# Track_Controller.net
KiCad netlist of a schematic drawn in EAGLE
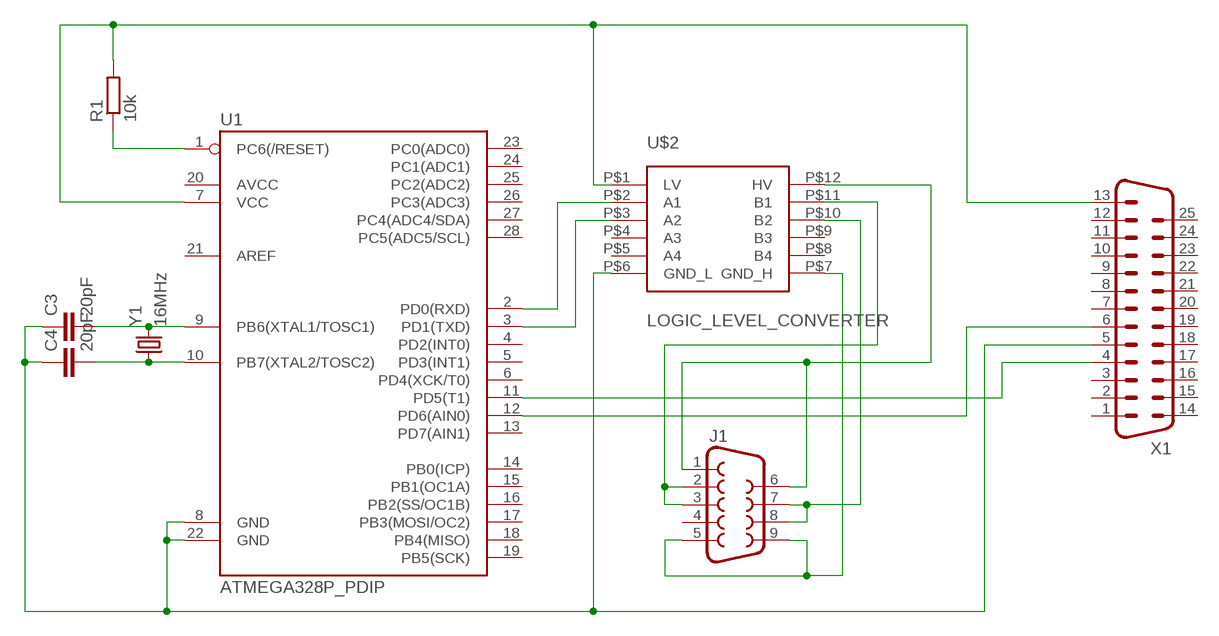
[diagram p0: schematic, sheet 1]
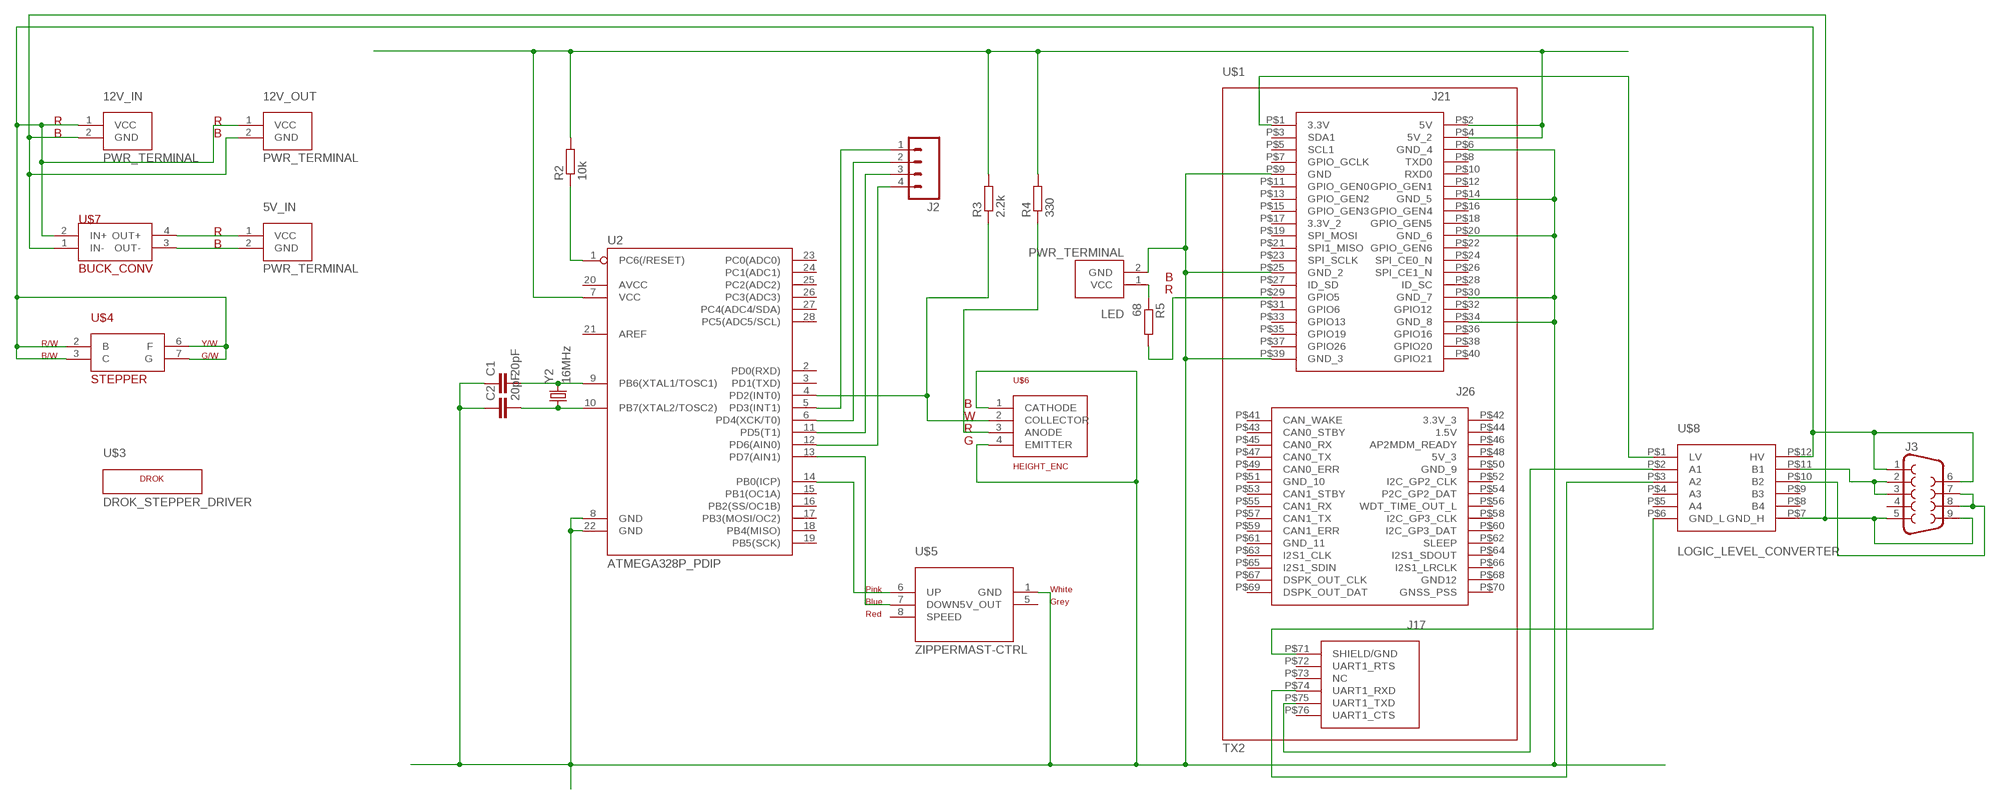
[diagram p1: schematic, sheet 2]

(export (version "E")
  (design (tool "Eeschema 10.0.6"))
  (components
    (comp (ref "5V_IN")
      (value "PWR_TERMINAL")
      (footprint "eagle-import:PWR_TERMINAL")
      (libsource (lib "eagle-import") (part "PWR_TERMINAL"))
    )
    (comp (ref "12V_IN")
      (value "PWR_TERMINAL")
      (footprint "eagle-import:PWR_TERMINAL")
      (libsource (lib "eagle-import") (part "PWR_TERMINAL"))
    )
    (comp (ref "12V_OUT")
      (value "PWR_TERMINAL")
      (footprint "eagle-import:PWR_TERMINAL")
      (libsource (lib "eagle-import") (part "PWR_TERMINAL"))
    )
    (comp (ref "C1")
      (value "20pF")
      (footprint "eagle-import:CAP-PTH-5MM")
      (libsource (lib "eagle-import") (part "CAPPTH1"))
    )
    (comp (ref "C2")
      (value "20pF")
      (footprint "eagle-import:CAP-PTH-5MM")
      (libsource (lib "eagle-import") (part "CAPPTH1"))
    )
    (comp (ref "J2")
      (value "M04PTH")
      (footprint "eagle-import:1X04")
      (libsource (lib "eagle-import") (part "M04PTH"))
    )
    (comp (ref "J3")
      (value "DB9MALE")
      (footprint "eagle-import:DB9_MALE")
      (libsource (lib "eagle-import") (part "DB9MALE"))
    )
    (comp (ref "LED")
      (value "PWR_TERMINAL")
      (footprint "eagle-import:PWR_TERMINAL")
      (libsource (lib "eagle-import") (part "PWR_TERMINAL"))
    )
    (comp (ref "R2")
      (value "10k")
      (footprint "eagle-import:0204_7")
      (libsource (lib "eagle-import") (part "R-EU_0204/7"))
    )
    (comp (ref "R3")
      (value "2.2k")
      (footprint "eagle-import:0204_7")
      (libsource (lib "eagle-import") (part "R-EU_0204/7"))
    )
    (comp (ref "R4")
      (value "330")
      (footprint "eagle-import:0204_7")
      (libsource (lib "eagle-import") (part "R-EU_0204/7"))
    )
    (comp (ref "R5")
      (value "68")
      (footprint "eagle-import:0204_7")
      (libsource (lib "eagle-import") (part "R-EU_0204/7"))
    )
    (comp (ref "U$1")
      (value "TX2")
      (footprint "eagle-import:TX2")
      (libsource (lib "eagle-import") (part "TX2"))
    )
    (comp (ref "U$3")
      (value "DROK_STEPPER_DRIVER")
      (footprint "eagle-import:DROK_STEPPER_DRIVER")
      (libsource (lib "eagle-import") (part "DROK_STEPPER_DRIVER"))
    )
    (comp (ref "U$4")
      (value "STEPPER")
      (footprint "eagle-import:STEPPER")
      (libsource (lib "eagle-import") (part "STEPPER"))
    )
    (comp (ref "U$5")
      (value "ZIPPERMAST-CTRL")
      (footprint "eagle-import:ZIPPERMAST-CTRL")
      (libsource (lib "eagle-import") (part "ZIPPERMAST-CTRL"))
    )
    (comp (ref "U$6")
      (value "HEIGHT_ENC")
      (footprint "eagle-import:HEIGHT_ENC")
      (libsource (lib "eagle-import") (part "HEIGHT_ENC"))
    )
    (comp (ref "U$7")
      (value "BUCK_CONV")
      (footprint "eagle-import:BUCK_CONV")
      (libsource (lib "eagle-import") (part "BUCK_CONV"))
    )
    (comp (ref "U$8")
      (value "LOGIC_LEVEL_CONVERTER")
      (footprint "eagle-import:LOGIC_LEVEL_CONVERTER")
      (libsource (lib "eagle-import") (part "LOGIC_LEVEL_CONVERTER"))
    )
    (comp (ref "U2")
      (value "ATMEGA328P_PDIP")
      (footprint "eagle-import:DIL28-3")
      (libsource (lib "eagle-import") (part "ATMEGA328P_PDIP"))
    )
    (comp (ref "Y2")
      (value "16MHz")
      (footprint "eagle-import:HC49US")
      (libsource (lib "eagle-import") (part "CRYSTALHC49US"))
    )
    (comp (ref "C3")
      (value "20pF")
      (footprint "eagle-import:CAP-PTH-5MM")
      (libsource (lib "eagle-import") (part "CAPPTH1"))
    )
    (comp (ref "C4")
      (value "20pF")
      (footprint "eagle-import:CAP-PTH-5MM")
      (libsource (lib "eagle-import") (part "CAPPTH1"))
    )
    (comp (ref "J1")
      (value "DB9FEMALE")
      (footprint "eagle-import:DB9")
      (libsource (lib "eagle-import") (part "DB9FEMALE"))
    )
    (comp (ref "R1")
      (value "10k")
      (footprint "eagle-import:0204_7")
      (libsource (lib "eagle-import") (part "R-EU_0204/7"))
    )
    (comp (ref "U$2")
      (value "LOGIC_LEVEL_CONVERTER")
      (footprint "eagle-import:LOGIC_LEVEL_CONVERTER")
      (libsource (lib "eagle-import") (part "LOGIC_LEVEL_CONVERTER"))
    )
    (comp (ref "U1")
      (value "ATMEGA328P_PDIP")
      (footprint "eagle-import:DIL28-3")
      (libsource (lib "eagle-import") (part "ATMEGA328P_PDIP"))
    )
    (comp (ref "X1")
      (value "DB25H")
      (footprint "eagle-import:M25H")
      (libsource (lib "eagle-import") (part "DB25H"))
    )
    (comp (ref "Y1")
      (value "16MHz")
      (footprint "eagle-import:HC49US")
      (libsource (lib "eagle-import") (part "CRYSTALHC49US"))
    )
  )
  (nets
    (net (code "1") (name "Net-(5V_IN-GND)") (class "Default")
      (node (ref "5V_IN") (pin "2") (pinfunction "GND_2") (pintype "bidirectional"))
      (node (ref "U$7") (pin "3") (pinfunction "OUT-_3") (pintype "bidirectional"))
    )
    (net (code "2") (name "Net-(5V_IN-VCC)") (class "Default")
      (node (ref "5V_IN") (pin "1") (pinfunction "VCC_1") (pintype "bidirectional"))
      (node (ref "U$7") (pin "4") (pinfunction "OUT+_4") (pintype "bidirectional"))
    )
    (net (code "3") (name "Net-(12V_IN-GND)") (class "Default")
      (node (ref "12V_IN") (pin "2") (pinfunction "GND_2") (pintype "bidirectional"))
      (node (ref "12V_OUT") (pin "2") (pinfunction "GND_2") (pintype "bidirectional"))
      (node (ref "J3") (pin "5") (pinfunction "5_5") (pintype "passive"))
      (node (ref "J3") (pin "9") (pinfunction "9_9") (pintype "passive"))
      (node (ref "U$7") (pin "1") (pinfunction "IN-_1") (pintype "bidirectional"))
      (node (ref "U$8") (pin "P$7") (pinfunction "GND_H_P$7") (pintype "bidirectional"))
    )
    (net (code "4") (name "Net-(12V_IN-VCC)") (class "Default")
      (node (ref "12V_IN") (pin "1") (pinfunction "VCC_1") (pintype "bidirectional"))
      (node (ref "12V_OUT") (pin "1") (pinfunction "VCC_1") (pintype "bidirectional"))
      (node (ref "J3") (pin "1") (pinfunction "1_1") (pintype "passive"))
      (node (ref "J3") (pin "6") (pinfunction "6_6") (pintype "passive"))
      (node (ref "U$4") (pin "2") (pinfunction "B_2") (pintype "bidirectional"))
      (node (ref "U$4") (pin "3") (pinfunction "C_3") (pintype "bidirectional"))
      (node (ref "U$4") (pin "6") (pinfunction "F_6") (pintype "bidirectional"))
      (node (ref "U$4") (pin "7") (pinfunction "G_7") (pintype "bidirectional"))
      (node (ref "U$7") (pin "2") (pinfunction "IN+_2") (pintype "bidirectional"))
      (node (ref "U$8") (pin "P$12") (pinfunction "HV_P$12") (pintype "bidirectional"))
    )
    (net (code "5") (name "Net-(LED-GND)") (class "Default")
      (node (ref "C1") (pin "1") (pinfunction "1_1") (pintype "passive"))
      (node (ref "C2") (pin "1") (pinfunction "1_1") (pintype "passive"))
      (node (ref "LED") (pin "2") (pinfunction "GND_2") (pintype "bidirectional"))
      (node (ref "U$1") (pin "P$14") (pinfunction "GND_5_P$14") (pintype "bidirectional"))
      (node (ref "U$1") (pin "P$20") (pinfunction "GND_6_P$20") (pintype "bidirectional"))
      (node (ref "U$1") (pin "P$25") (pinfunction "GND_2_P$25") (pintype "bidirectional"))
      (node (ref "U$1") (pin "P$30") (pinfunction "GND_7_P$30") (pintype "bidirectional"))
      (node (ref "U$1") (pin "P$34") (pinfunction "GND_8_P$34") (pintype "bidirectional"))
      (node (ref "U$1") (pin "P$39") (pinfunction "GND_3_P$39") (pintype "bidirectional"))
      (node (ref "U$1") (pin "P$6") (pinfunction "GND_4_P$6") (pintype "bidirectional"))
      (node (ref "U$1") (pin "P$9") (pinfunction "GND_P$9") (pintype "bidirectional"))
      (node (ref "U$5") (pin "1") (pinfunction "GND_1") (pintype "bidirectional"))
      (node (ref "U$6") (pin "1") (pinfunction "CATHODE_1") (pintype "bidirectional"))
      (node (ref "U$6") (pin "4") (pinfunction "EMITTER_4") (pintype "bidirectional"))
      (node (ref "U2") (pin "22") (pinfunction "GND_22") (pintype "bidirectional"))
      (node (ref "U2") (pin "8") (pinfunction "GND_8") (pintype "bidirectional"))
    )
    (net (code "6") (name "Net-(LED-VCC)") (class "Default")
      (node (ref "LED") (pin "1") (pinfunction "VCC_1") (pintype "bidirectional"))
      (node (ref "R5") (pin "1") (pinfunction "1_1") (pintype "passive"))
    )
    (net (code "7") (name "Net-(U$1-3.3V)") (class "Default")
      (node (ref "U$1") (pin "P$1") (pinfunction "3.3V_P$1") (pintype "bidirectional"))
      (node (ref "U$8") (pin "P$1") (pinfunction "LV_P$1") (pintype "bidirectional"))
    )
    (net (code "8") (name "Net-(U$1-5V)") (class "Default")
      (node (ref "R2") (pin "2") (pinfunction "2_2") (pintype "passive"))
      (node (ref "R3") (pin "2") (pinfunction "2_2") (pintype "passive"))
      (node (ref "R4") (pin "2") (pinfunction "2_2") (pintype "passive"))
      (node (ref "U$1") (pin "P$2") (pinfunction "5V_P$2") (pintype "bidirectional"))
      (node (ref "U$1") (pin "P$4") (pinfunction "5V_2_P$4") (pintype "bidirectional"))
      (node (ref "U2") (pin "7") (pinfunction "VCC_7") (pintype "bidirectional"))
    )
    (net (code "9") (name "Net-(U$1-GPIO5)") (class "Default")
      (node (ref "R5") (pin "2") (pinfunction "2_2") (pintype "passive"))
      (node (ref "U$1") (pin "P$29") (pinfunction "GPIO5_P$29") (pintype "bidirectional"))
    )
    (net (code "10") (name "Net-(U$1-SHIELD{slash}GND)") (class "Default")
      (node (ref "U$1") (pin "P$71") (pinfunction "SHIELD/GND_P$71") (pintype "bidirectional"))
      (node (ref "U$8") (pin "P$6") (pinfunction "GND_L_P$6") (pintype "bidirectional"))
    )
    (net (code "11") (name "Net-(U$1-UART1_RXD)") (class "Default")
      (node (ref "U$1") (pin "P$74") (pinfunction "UART1_RXD_P$74") (pintype "bidirectional"))
      (node (ref "U$8") (pin "P$3") (pinfunction "A2_P$3") (pintype "bidirectional"))
    )
    (net (code "12") (name "Net-(U$1-UART1_TXD)") (class "Default")
      (node (ref "U$1") (pin "P$75") (pinfunction "UART1_TXD_P$75") (pintype "bidirectional"))
      (node (ref "U$8") (pin "P$2") (pinfunction "A1_P$2") (pintype "bidirectional"))
    )
    (net (code "13") (name "Net-(U$2-A1)") (class "Default")
      (node (ref "U$2") (pin "P$2") (pinfunction "A1_P$2") (pintype "bidirectional"))
      (node (ref "U1") (pin "2") (pinfunction "PD0(RXD)_2") (pintype "bidirectional"))
    )
    (net (code "14") (name "Net-(U$2-A2)") (class "Default")
      (node (ref "U$2") (pin "P$3") (pinfunction "A2_P$3") (pintype "bidirectional"))
      (node (ref "U1") (pin "3") (pinfunction "PD1(TXD)_3") (pintype "bidirectional"))
    )
    (net (code "15") (name "Net-(U$2-B1)") (class "Default")
      (node (ref "J1") (pin "2") (pinfunction "2_2") (pintype "passive"))
      (node (ref "J1") (pin "3") (pinfunction "3_3") (pintype "passive"))
      (node (ref "U$2") (pin "P$11") (pinfunction "B1_P$11") (pintype "bidirectional"))
    )
    (net (code "16") (name "Net-(U$2-B2)") (class "Default")
      (node (ref "J1") (pin "7") (pinfunction "7_7") (pintype "passive"))
      (node (ref "J1") (pin "8") (pinfunction "8_8") (pintype "passive"))
      (node (ref "U$2") (pin "P$10") (pinfunction "B2_P$10") (pintype "bidirectional"))
    )
    (net (code "17") (name "Net-(U$2-GND_H)") (class "Default")
      (node (ref "J1") (pin "5") (pinfunction "5_5") (pintype "passive"))
      (node (ref "J1") (pin "9") (pinfunction "9_9") (pintype "passive"))
      (node (ref "U$2") (pin "P$7") (pinfunction "GND_H_P$7") (pintype "bidirectional"))
    )
    (net (code "18") (name "Net-(U$2-GND_L)") (class "Default")
      (node (ref "C3") (pin "1") (pinfunction "1_1") (pintype "passive"))
      (node (ref "C4") (pin "1") (pinfunction "1_1") (pintype "passive"))
      (node (ref "U$2") (pin "P$6") (pinfunction "GND_L_P$6") (pintype "bidirectional"))
      (node (ref "U1") (pin "22") (pinfunction "GND_22") (pintype "bidirectional"))
      (node (ref "U1") (pin "8") (pinfunction "GND_8") (pintype "bidirectional"))
      (node (ref "X1") (pin "5") (pinfunction "5_5") (pintype "passive"))
    )
    (net (code "19") (name "Net-(U$2-HV)") (class "Default")
      (node (ref "J1") (pin "1") (pinfunction "1_1") (pintype "passive"))
      (node (ref "J1") (pin "6") (pinfunction "6_6") (pintype "passive"))
      (node (ref "U$2") (pin "P$12") (pinfunction "HV_P$12") (pintype "bidirectional"))
    )
    (net (code "20") (name "Net-(U$2-LV)") (class "Default")
      (node (ref "R1") (pin "2") (pinfunction "2_2") (pintype "passive"))
      (node (ref "U$2") (pin "P$1") (pinfunction "LV_P$1") (pintype "bidirectional"))
      (node (ref "U1") (pin "7") (pinfunction "VCC_7") (pintype "bidirectional"))
      (node (ref "X1") (pin "13") (pinfunction "13_13") (pintype "passive"))
    )
    (net (code "21") (name "Net-(U$5-DOWN)") (class "Default")
      (node (ref "U$5") (pin "7") (pinfunction "DOWN_7") (pintype "bidirectional"))
      (node (ref "U2") (pin "13") (pinfunction "PD7(AIN1)_13") (pintype "bidirectional"))
    )
    (net (code "22") (name "Net-(U$5-UP)") (class "Default")
      (node (ref "U$5") (pin "6") (pinfunction "UP_6") (pintype "bidirectional"))
      (node (ref "U2") (pin "14") (pinfunction "PB0(ICP)_14") (pintype "bidirectional"))
    )
    (net (code "23") (name "Net-(U$6-ANODE)") (class "Default")
      (node (ref "R4") (pin "1") (pinfunction "1_1") (pintype "passive"))
      (node (ref "U$6") (pin "3") (pinfunction "ANODE_3") (pintype "bidirectional"))
    )
    (net (code "24") (name "Net-(U$6-COLLECTOR)") (class "Default")
      (node (ref "R3") (pin "1") (pinfunction "1_1") (pintype "passive"))
      (node (ref "U$6") (pin "2") (pinfunction "COLLECTOR_2") (pintype "bidirectional"))
      (node (ref "U2") (pin "4") (pinfunction "PD2(INT0)_4") (pintype "bidirectional"))
    )
    (net (code "25") (name "Net-(U$8-B1)") (class "Default")
      (node (ref "J3") (pin "2") (pinfunction "2_2") (pintype "passive"))
      (node (ref "J3") (pin "3") (pinfunction "3_3") (pintype "passive"))
      (node (ref "U$8") (pin "P$11") (pinfunction "B1_P$11") (pintype "bidirectional"))
    )
    (net (code "26") (name "Net-(U$8-B2)") (class "Default")
      (node (ref "J3") (pin "7") (pinfunction "7_7") (pintype "passive"))
      (node (ref "J3") (pin "8") (pinfunction "8_8") (pintype "passive"))
      (node (ref "U$8") (pin "P$10") (pinfunction "B2_P$10") (pintype "bidirectional"))
    )
    (net (code "27") (name "Net-(U1-PB6(XTAL1{slash}TOSC1))") (class "Default")
      (node (ref "C3") (pin "2") (pinfunction "2_2") (pintype "passive"))
      (node (ref "U1") (pin "9") (pinfunction "PB6(XTAL1/TOSC1)_9") (pintype "bidirectional"))
      (node (ref "Y1") (pin "2") (pinfunction "2_2") (pintype "passive"))
    )
    (net (code "28") (name "Net-(U1-PB7(XTAL2{slash}TOSC2))") (class "Default")
      (node (ref "C4") (pin "2") (pinfunction "2_2") (pintype "passive"))
      (node (ref "U1") (pin "10") (pinfunction "PB7(XTAL2/TOSC2)_10") (pintype "bidirectional"))
      (node (ref "Y1") (pin "1") (pinfunction "1_1") (pintype "passive"))
    )
    (net (code "29") (name "Net-(U1-PC6({slash}RESET))") (class "Default")
      (node (ref "R1") (pin "1") (pinfunction "1_1") (pintype "passive"))
      (node (ref "U1") (pin "1") (pinfunction "PC6(/RESET)_1") (pintype "bidirectional"))
    )
    (net (code "30") (name "Net-(U1-PD5(T1))") (class "Default")
      (node (ref "U1") (pin "11") (pinfunction "PD5(T1)_11") (pintype "bidirectional"))
      (node (ref "X1") (pin "4") (pinfunction "4_4") (pintype "passive"))
    )
    (net (code "31") (name "Net-(U1-PD6(AIN0))") (class "Default")
      (node (ref "U1") (pin "12") (pinfunction "PD6(AIN0)_12") (pintype "bidirectional"))
      (node (ref "X1") (pin "6") (pinfunction "6_6") (pintype "passive"))
    )
    (net (code "32") (name "Net-(U2-PB6(XTAL1{slash}TOSC1))") (class "Default")
      (node (ref "C1") (pin "2") (pinfunction "2_2") (pintype "passive"))
      (node (ref "U2") (pin "9") (pinfunction "PB6(XTAL1/TOSC1)_9") (pintype "bidirectional"))
      (node (ref "Y2") (pin "2") (pinfunction "2_2") (pintype "passive"))
    )
    (net (code "33") (name "Net-(U2-PB7(XTAL2{slash}TOSC2))") (class "Default")
      (node (ref "C2") (pin "2") (pinfunction "2_2") (pintype "passive"))
      (node (ref "U2") (pin "10") (pinfunction "PB7(XTAL2/TOSC2)_10") (pintype "bidirectional"))
      (node (ref "Y2") (pin "1") (pinfunction "1_1") (pintype "passive"))
    )
    (net (code "34") (name "Net-(U2-PC6({slash}RESET))") (class "Default")
      (node (ref "R2") (pin "1") (pinfunction "1_1") (pintype "passive"))
      (node (ref "U2") (pin "1") (pinfunction "PC6(/RESET)_1") (pintype "bidirectional"))
    )
    (net (code "35") (name "Net-(U2-PD3(INT1))") (class "Default")
      (node (ref "J2") (pin "1") (pinfunction "1_1") (pintype "passive"))
      (node (ref "U2") (pin "5") (pinfunction "PD3(INT1)_5") (pintype "bidirectional"))
    )
    (net (code "36") (name "Net-(U2-PD4(XCK{slash}T0))") (class "Default")
      (node (ref "J2") (pin "2") (pinfunction "2_2") (pintype "passive"))
      (node (ref "U2") (pin "6") (pinfunction "PD4(XCK/T0)_6") (pintype "bidirectional"))
    )
    (net (code "37") (name "Net-(U2-PD5(T1))") (class "Default")
      (node (ref "J2") (pin "3") (pinfunction "3_3") (pintype "passive"))
      (node (ref "U2") (pin "11") (pinfunction "PD5(T1)_11") (pintype "bidirectional"))
    )
    (net (code "38") (name "Net-(U2-PD6(AIN0))") (class "Default")
      (node (ref "J2") (pin "4") (pinfunction "4_4") (pintype "passive"))
      (node (ref "U2") (pin "12") (pinfunction "PD6(AIN0)_12") (pintype "bidirectional"))
    )
    (net (code "39") (name "unconnected-(J1-Pad4)") (class "Default")
      (node (ref "J1") (pin "4") (pinfunction "4_4") (pintype "passive"))
    )
    (net (code "40") (name "unconnected-(J3-Pad4)") (class "Default")
      (node (ref "J3") (pin "4") (pinfunction "4_4") (pintype "passive"))
    )
    (net (code "41") (name "unconnected-(U$1-1.5V-PadP$44)") (class "Default")
      (node (ref "U$1") (pin "P$44") (pinfunction "1.5V_P$44") (pintype "bidirectional"))
    )
    (net (code "42") (name "unconnected-(U$1-3.3V_2-PadP$17)") (class "Default")
      (node (ref "U$1") (pin "P$17") (pinfunction "3.3V_2_P$17") (pintype "bidirectional"))
    )
    (net (code "43") (name "unconnected-(U$1-3.3V_3-PadP$42)") (class "Default")
      (node (ref "U$1") (pin "P$42") (pinfunction "3.3V_3_P$42") (pintype "bidirectional"))
    )
    (net (code "44") (name "unconnected-(U$1-5V_3-PadP$48)") (class "Default")
      (node (ref "U$1") (pin "P$48") (pinfunction "5V_3_P$48") (pintype "bidirectional"))
    )
    (net (code "45") (name "unconnected-(U$1-AP2MDM_READY-PadP$46)") (class "Default")
      (node (ref "U$1") (pin "P$46") (pinfunction "AP2MDM_READY_P$46") (pintype "bidirectional"))
    )
    (net (code "46") (name "unconnected-(U$1-CAN0_ERR-PadP$49)") (class "Default")
      (node (ref "U$1") (pin "P$49") (pinfunction "CAN0_ERR_P$49") (pintype "bidirectional"))
    )
    (net (code "47") (name "unconnected-(U$1-CAN0_RX-PadP$45)") (class "Default")
      (node (ref "U$1") (pin "P$45") (pinfunction "CAN0_RX_P$45") (pintype "bidirectional"))
    )
    (net (code "48") (name "unconnected-(U$1-CAN0_STBY-PadP$43)") (class "Default")
      (node (ref "U$1") (pin "P$43") (pinfunction "CAN0_STBY_P$43") (pintype "bidirectional"))
    )
    (net (code "49") (name "unconnected-(U$1-CAN0_TX-PadP$47)") (class "Default")
      (node (ref "U$1") (pin "P$47") (pinfunction "CAN0_TX_P$47") (pintype "bidirectional"))
    )
    (net (code "50") (name "unconnected-(U$1-CAN1_ERR-PadP$59)") (class "Default")
      (node (ref "U$1") (pin "P$59") (pinfunction "CAN1_ERR_P$59") (pintype "bidirectional"))
    )
    (net (code "51") (name "unconnected-(U$1-CAN1_RX-PadP$55)") (class "Default")
      (node (ref "U$1") (pin "P$55") (pinfunction "CAN1_RX_P$55") (pintype "bidirectional"))
    )
    (net (code "52") (name "unconnected-(U$1-CAN1_STBY-PadP$53)") (class "Default")
      (node (ref "U$1") (pin "P$53") (pinfunction "CAN1_STBY_P$53") (pintype "bidirectional"))
    )
    (net (code "53") (name "unconnected-(U$1-CAN1_TX-PadP$57)") (class "Default")
      (node (ref "U$1") (pin "P$57") (pinfunction "CAN1_TX_P$57") (pintype "bidirectional"))
    )
    (net (code "54") (name "unconnected-(U$1-CAN_WAKE-PadP$41)") (class "Default")
      (node (ref "U$1") (pin "P$41") (pinfunction "CAN_WAKE_P$41") (pintype "bidirectional"))
    )
    (net (code "55") (name "unconnected-(U$1-DSPK_OUT_CLK-PadP$67)") (class "Default")
      (node (ref "U$1") (pin "P$67") (pinfunction "DSPK_OUT_CLK_P$67") (pintype "bidirectional"))
    )
    (net (code "56") (name "unconnected-(U$1-DSPK_OUT_DAT-PadP$69)") (class "Default")
      (node (ref "U$1") (pin "P$69") (pinfunction "DSPK_OUT_DAT_P$69") (pintype "bidirectional"))
    )
    (net (code "57") (name "unconnected-(U$1-GND12-PadP$68)") (class "Default")
      (node (ref "U$1") (pin "P$68") (pinfunction "GND12_P$68") (pintype "bidirectional"))
    )
    (net (code "58") (name "unconnected-(U$1-GND_9-PadP$50)") (class "Default")
      (node (ref "U$1") (pin "P$50") (pinfunction "GND_9_P$50") (pintype "bidirectional"))
    )
    (net (code "59") (name "unconnected-(U$1-GND_10-PadP$51)") (class "Default")
      (node (ref "U$1") (pin "P$51") (pinfunction "GND_10_P$51") (pintype "bidirectional"))
    )
    (net (code "60") (name "unconnected-(U$1-GND_11-PadP$61)") (class "Default")
      (node (ref "U$1") (pin "P$61") (pinfunction "GND_11_P$61") (pintype "bidirectional"))
    )
    (net (code "61") (name "unconnected-(U$1-GNSS_PSS-PadP$70)") (class "Default")
      (node (ref "U$1") (pin "P$70") (pinfunction "GNSS_PSS_P$70") (pintype "bidirectional"))
    )
    (net (code "62") (name "unconnected-(U$1-GPIO6-PadP$31)") (class "Default")
      (node (ref "U$1") (pin "P$31") (pinfunction "GPIO6_P$31") (pintype "bidirectional"))
    )
    (net (code "63") (name "unconnected-(U$1-GPIO12-PadP$32)") (class "Default")
      (node (ref "U$1") (pin "P$32") (pinfunction "GPIO12_P$32") (pintype "bidirectional"))
    )
    (net (code "64") (name "unconnected-(U$1-GPIO13-PadP$33)") (class "Default")
      (node (ref "U$1") (pin "P$33") (pinfunction "GPIO13_P$33") (pintype "bidirectional"))
    )
    (net (code "65") (name "unconnected-(U$1-GPIO16-PadP$36)") (class "Default")
      (node (ref "U$1") (pin "P$36") (pinfunction "GPIO16_P$36") (pintype "bidirectional"))
    )
    (net (code "66") (name "unconnected-(U$1-GPIO19-PadP$35)") (class "Default")
      (node (ref "U$1") (pin "P$35") (pinfunction "GPIO19_P$35") (pintype "bidirectional"))
    )
    (net (code "67") (name "unconnected-(U$1-GPIO20-PadP$38)") (class "Default")
      (node (ref "U$1") (pin "P$38") (pinfunction "GPIO20_P$38") (pintype "bidirectional"))
    )
    (net (code "68") (name "unconnected-(U$1-GPIO21-PadP$40)") (class "Default")
      (node (ref "U$1") (pin "P$40") (pinfunction "GPIO21_P$40") (pintype "bidirectional"))
    )
    (net (code "69") (name "unconnected-(U$1-GPIO26-PadP$37)") (class "Default")
      (node (ref "U$1") (pin "P$37") (pinfunction "GPIO26_P$37") (pintype "bidirectional"))
    )
    (net (code "70") (name "unconnected-(U$1-GPIO_GCLK-PadP$7)") (class "Default")
      (node (ref "U$1") (pin "P$7") (pinfunction "GPIO_GCLK_P$7") (pintype "bidirectional"))
    )
    (net (code "71") (name "unconnected-(U$1-GPIO_GEN0-PadP$11)") (class "Default")
      (node (ref "U$1") (pin "P$11") (pinfunction "GPIO_GEN0_P$11") (pintype "bidirectional"))
    )
    (net (code "72") (name "unconnected-(U$1-GPIO_GEN1-PadP$12)") (class "Default")
      (node (ref "U$1") (pin "P$12") (pinfunction "GPIO_GEN1_P$12") (pintype "bidirectional"))
    )
    (net (code "73") (name "unconnected-(U$1-GPIO_GEN2-PadP$13)") (class "Default")
      (node (ref "U$1") (pin "P$13") (pinfunction "GPIO_GEN2_P$13") (pintype "bidirectional"))
    )
    (net (code "74") (name "unconnected-(U$1-GPIO_GEN3-PadP$15)") (class "Default")
      (node (ref "U$1") (pin "P$15") (pinfunction "GPIO_GEN3_P$15") (pintype "bidirectional"))
    )
    (net (code "75") (name "unconnected-(U$1-GPIO_GEN4-PadP$16)") (class "Default")
      (node (ref "U$1") (pin "P$16") (pinfunction "GPIO_GEN4_P$16") (pintype "bidirectional"))
    )
    (net (code "76") (name "unconnected-(U$1-GPIO_GEN5-PadP$18)") (class "Default")
      (node (ref "U$1") (pin "P$18") (pinfunction "GPIO_GEN5_P$18") (pintype "bidirectional"))
    )
    (net (code "77") (name "unconnected-(U$1-GPIO_GEN6-PadP$22)") (class "Default")
      (node (ref "U$1") (pin "P$22") (pinfunction "GPIO_GEN6_P$22") (pintype "bidirectional"))
    )
    (net (code "78") (name "unconnected-(U$1-I2C_GP2_CLK-PadP$52)") (class "Default")
      (node (ref "U$1") (pin "P$52") (pinfunction "I2C_GP2_CLK_P$52") (pintype "bidirectional"))
    )
    (net (code "79") (name "unconnected-(U$1-I2C_GP3_CLK-PadP$58)") (class "Default")
      (node (ref "U$1") (pin "P$58") (pinfunction "I2C_GP3_CLK_P$58") (pintype "bidirectional"))
    )
    (net (code "80") (name "unconnected-(U$1-I2C_GP3_DAT-PadP$60)") (class "Default")
      (node (ref "U$1") (pin "P$60") (pinfunction "I2C_GP3_DAT_P$60") (pintype "bidirectional"))
    )
    (net (code "81") (name "unconnected-(U$1-I2S1_CLK-PadP$63)") (class "Default")
      (node (ref "U$1") (pin "P$63") (pinfunction "I2S1_CLK_P$63") (pintype "bidirectional"))
    )
    (net (code "82") (name "unconnected-(U$1-I2S1_LRCLK-PadP$66)") (class "Default")
      (node (ref "U$1") (pin "P$66") (pinfunction "I2S1_LRCLK_P$66") (pintype "bidirectional"))
    )
    (net (code "83") (name "unconnected-(U$1-I2S1_SDIN-PadP$65)") (class "Default")
      (node (ref "U$1") (pin "P$65") (pinfunction "I2S1_SDIN_P$65") (pintype "bidirectional"))
    )
    (net (code "84") (name "unconnected-(U$1-I2S1_SDOUT-PadP$64)") (class "Default")
      (node (ref "U$1") (pin "P$64") (pinfunction "I2S1_SDOUT_P$64") (pintype "bidirectional"))
    )
    (net (code "85") (name "unconnected-(U$1-ID_SC-PadP$28)") (class "Default")
      (node (ref "U$1") (pin "P$28") (pinfunction "ID_SC_P$28") (pintype "bidirectional"))
    )
    (net (code "86") (name "unconnected-(U$1-ID_SD-PadP$27)") (class "Default")
      (node (ref "U$1") (pin "P$27") (pinfunction "ID_SD_P$27") (pintype "bidirectional"))
    )
    (net (code "87") (name "unconnected-(U$1-NC-PadP$73)") (class "Default")
      (node (ref "U$1") (pin "P$73") (pinfunction "NC_P$73") (pintype "bidirectional"))
    )
    (net (code "88") (name "unconnected-(U$1-P2C_GP2_DAT-PadP$54)") (class "Default")
      (node (ref "U$1") (pin "P$54") (pinfunction "P2C_GP2_DAT_P$54") (pintype "bidirectional"))
    )
    (net (code "89") (name "unconnected-(U$1-RXD0-PadP$10)") (class "Default")
      (node (ref "U$1") (pin "P$10") (pinfunction "RXD0_P$10") (pintype "bidirectional"))
    )
    (net (code "90") (name "unconnected-(U$1-SCL1-PadP$5)") (class "Default")
      (node (ref "U$1") (pin "P$5") (pinfunction "SCL1_P$5") (pintype "bidirectional"))
    )
    (net (code "91") (name "unconnected-(U$1-SDA1-PadP$3)") (class "Default")
      (node (ref "U$1") (pin "P$3") (pinfunction "SDA1_P$3") (pintype "bidirectional"))
    )
    (net (code "92") (name "unconnected-(U$1-SLEEP-PadP$62)") (class "Default")
      (node (ref "U$1") (pin "P$62") (pinfunction "SLEEP_P$62") (pintype "bidirectional"))
    )
    (net (code "93") (name "unconnected-(U$1-SPI1_MISO-PadP$21)") (class "Default")
      (node (ref "U$1") (pin "P$21") (pinfunction "SPI1_MISO_P$21") (pintype "bidirectional"))
    )
    (net (code "94") (name "unconnected-(U$1-SPI_CE0_N-PadP$24)") (class "Default")
      (node (ref "U$1") (pin "P$24") (pinfunction "SPI_CE0_N_P$24") (pintype "bidirectional"))
    )
    (net (code "95") (name "unconnected-(U$1-SPI_CE1_N-PadP$26)") (class "Default")
      (node (ref "U$1") (pin "P$26") (pinfunction "SPI_CE1_N_P$26") (pintype "bidirectional"))
    )
    (net (code "96") (name "unconnected-(U$1-SPI_MOSI-PadP$19)") (class "Default")
      (node (ref "U$1") (pin "P$19") (pinfunction "SPI_MOSI_P$19") (pintype "bidirectional"))
    )
    (net (code "97") (name "unconnected-(U$1-SPI_SCLK-PadP$23)") (class "Default")
      (node (ref "U$1") (pin "P$23") (pinfunction "SPI_SCLK_P$23") (pintype "bidirectional"))
    )
    (net (code "98") (name "unconnected-(U$1-TXD0-PadP$8)") (class "Default")
      (node (ref "U$1") (pin "P$8") (pinfunction "TXD0_P$8") (pintype "bidirectional"))
    )
    (net (code "99") (name "unconnected-(U$1-UART1_CTS-PadP$76)") (class "Default")
      (node (ref "U$1") (pin "P$76") (pinfunction "UART1_CTS_P$76") (pintype "bidirectional"))
    )
    (net (code "100") (name "unconnected-(U$1-UART1_RTS-PadP$72)") (class "Default")
      (node (ref "U$1") (pin "P$72") (pinfunction "UART1_RTS_P$72") (pintype "bidirectional"))
    )
    (net (code "101") (name "unconnected-(U$1-WDT_TIME_OUT_L-PadP$56)") (class "Default")
      (node (ref "U$1") (pin "P$56") (pinfunction "WDT_TIME_OUT_L_P$56") (pintype "bidirectional"))
    )
    (net (code "102") (name "unconnected-(U$2-A3-PadP$4)") (class "Default")
      (node (ref "U$2") (pin "P$4") (pinfunction "A3_P$4") (pintype "bidirectional"))
    )
    (net (code "103") (name "unconnected-(U$2-A4-PadP$5)") (class "Default")
      (node (ref "U$2") (pin "P$5") (pinfunction "A4_P$5") (pintype "bidirectional"))
    )
    (net (code "104") (name "unconnected-(U$2-B3-PadP$9)") (class "Default")
      (node (ref "U$2") (pin "P$9") (pinfunction "B3_P$9") (pintype "bidirectional"))
    )
    (net (code "105") (name "unconnected-(U$2-B4-PadP$8)") (class "Default")
      (node (ref "U$2") (pin "P$8") (pinfunction "B4_P$8") (pintype "bidirectional"))
    )
    (net (code "106") (name "unconnected-(U$5-5V_OUT-Pad5)") (class "Default")
      (node (ref "U$5") (pin "5") (pinfunction "5V_OUT_5") (pintype "bidirectional"))
    )
    (net (code "107") (name "unconnected-(U$5-SPEED-Pad8)") (class "Default")
      (node (ref "U$5") (pin "8") (pinfunction "SPEED_8") (pintype "bidirectional"))
    )
    (net (code "108") (name "unconnected-(U$8-A3-PadP$4)") (class "Default")
      (node (ref "U$8") (pin "P$4") (pinfunction "A3_P$4") (pintype "bidirectional"))
    )
    (net (code "109") (name "unconnected-(U$8-A4-PadP$5)") (class "Default")
      (node (ref "U$8") (pin "P$5") (pinfunction "A4_P$5") (pintype "bidirectional"))
    )
    (net (code "110") (name "unconnected-(U$8-B3-PadP$9)") (class "Default")
      (node (ref "U$8") (pin "P$9") (pinfunction "B3_P$9") (pintype "bidirectional"))
    )
    (net (code "111") (name "unconnected-(U$8-B4-PadP$8)") (class "Default")
      (node (ref "U$8") (pin "P$8") (pinfunction "B4_P$8") (pintype "bidirectional"))
    )
    (net (code "112") (name "unconnected-(U1-AREF-Pad21)") (class "Default")
      (node (ref "U1") (pin "21") (pinfunction "AREF_21") (pintype "bidirectional"))
    )
    (net (code "113") (name "unconnected-(U1-AVCC-Pad20)") (class "Default")
      (node (ref "U1") (pin "20") (pinfunction "AVCC_20") (pintype "bidirectional"))
    )
    (net (code "114") (name "unconnected-(U1-PB0(ICP)-Pad14)") (class "Default")
      (node (ref "U1") (pin "14") (pinfunction "PB0(ICP)_14") (pintype "bidirectional"))
    )
    (net (code "115") (name "unconnected-(U1-PB1(OC1A)-Pad15)") (class "Default")
      (node (ref "U1") (pin "15") (pinfunction "PB1(OC1A)_15") (pintype "bidirectional"))
    )
    (net (code "116") (name "unconnected-(U1-PB2(SS{slash}OC1B)-Pad16)") (class "Default")
      (node (ref "U1") (pin "16") (pinfunction "PB2(SS/OC1B)_16") (pintype "bidirectional"))
    )
    (net (code "117") (name "unconnected-(U1-PB3(MOSI{slash}OC2)-Pad17)") (class "Default")
      (node (ref "U1") (pin "17") (pinfunction "PB3(MOSI/OC2)_17") (pintype "bidirectional"))
    )
    (net (code "118") (name "unconnected-(U1-PB4(MISO)-Pad18)") (class "Default")
      (node (ref "U1") (pin "18") (pinfunction "PB4(MISO)_18") (pintype "bidirectional"))
    )
    (net (code "119") (name "unconnected-(U1-PB5(SCK)-Pad19)") (class "Default")
      (node (ref "U1") (pin "19") (pinfunction "PB5(SCK)_19") (pintype "bidirectional"))
    )
    (net (code "120") (name "unconnected-(U1-PC0(ADC0)-Pad23)") (class "Default")
      (node (ref "U1") (pin "23") (pinfunction "PC0(ADC0)_23") (pintype "bidirectional"))
    )
    (net (code "121") (name "unconnected-(U1-PC1(ADC1)-Pad24)") (class "Default")
      (node (ref "U1") (pin "24") (pinfunction "PC1(ADC1)_24") (pintype "bidirectional"))
    )
    (net (code "122") (name "unconnected-(U1-PC2(ADC2)-Pad25)") (class "Default")
      (node (ref "U1") (pin "25") (pinfunction "PC2(ADC2)_25") (pintype "bidirectional"))
    )
    (net (code "123") (name "unconnected-(U1-PC3(ADC3)-Pad26)") (class "Default")
      (node (ref "U1") (pin "26") (pinfunction "PC3(ADC3)_26") (pintype "bidirectional"))
    )
    (net (code "124") (name "unconnected-(U1-PC4(ADC4{slash}SDA)-Pad27)") (class "Default")
      (node (ref "U1") (pin "27") (pinfunction "PC4(ADC4/SDA)_27") (pintype "bidirectional"))
    )
    (net (code "125") (name "unconnected-(U1-PC5(ADC5{slash}SCL)-Pad28)") (class "Default")
      (node (ref "U1") (pin "28") (pinfunction "PC5(ADC5/SCL)_28") (pintype "bidirectional"))
    )
    (net (code "126") (name "unconnected-(U1-PD2(INT0)-Pad4)") (class "Default")
      (node (ref "U1") (pin "4") (pinfunction "PD2(INT0)_4") (pintype "bidirectional"))
    )
    (net (code "127") (name "unconnected-(U1-PD3(INT1)-Pad5)") (class "Default")
      (node (ref "U1") (pin "5") (pinfunction "PD3(INT1)_5") (pintype "bidirectional"))
    )
    (net (code "128") (name "unconnected-(U1-PD4(XCK{slash}T0)-Pad6)") (class "Default")
      (node (ref "U1") (pin "6") (pinfunction "PD4(XCK/T0)_6") (pintype "bidirectional"))
    )
    (net (code "129") (name "unconnected-(U1-PD7(AIN1)-Pad13)") (class "Default")
      (node (ref "U1") (pin "13") (pinfunction "PD7(AIN1)_13") (pintype "bidirectional"))
    )
    (net (code "130") (name "unconnected-(U2-AREF-Pad21)") (class "Default")
      (node (ref "U2") (pin "21") (pinfunction "AREF_21") (pintype "bidirectional"))
    )
    (net (code "131") (name "unconnected-(U2-AVCC-Pad20)") (class "Default")
      (node (ref "U2") (pin "20") (pinfunction "AVCC_20") (pintype "bidirectional"))
    )
    (net (code "132") (name "unconnected-(U2-PB1(OC1A)-Pad15)") (class "Default")
      (node (ref "U2") (pin "15") (pinfunction "PB1(OC1A)_15") (pintype "bidirectional"))
    )
    (net (code "133") (name "unconnected-(U2-PB2(SS{slash}OC1B)-Pad16)") (class "Default")
      (node (ref "U2") (pin "16") (pinfunction "PB2(SS/OC1B)_16") (pintype "bidirectional"))
    )
    (net (code "134") (name "unconnected-(U2-PB3(MOSI{slash}OC2)-Pad17)") (class "Default")
      (node (ref "U2") (pin "17") (pinfunction "PB3(MOSI/OC2)_17") (pintype "bidirectional"))
    )
    (net (code "135") (name "unconnected-(U2-PB4(MISO)-Pad18)") (class "Default")
      (node (ref "U2") (pin "18") (pinfunction "PB4(MISO)_18") (pintype "bidirectional"))
    )
    (net (code "136") (name "unconnected-(U2-PB5(SCK)-Pad19)") (class "Default")
      (node (ref "U2") (pin "19") (pinfunction "PB5(SCK)_19") (pintype "bidirectional"))
    )
    (net (code "137") (name "unconnected-(U2-PC0(ADC0)-Pad23)") (class "Default")
      (node (ref "U2") (pin "23") (pinfunction "PC0(ADC0)_23") (pintype "bidirectional"))
    )
    (net (code "138") (name "unconnected-(U2-PC1(ADC1)-Pad24)") (class "Default")
      (node (ref "U2") (pin "24") (pinfunction "PC1(ADC1)_24") (pintype "bidirectional"))
    )
    (net (code "139") (name "unconnected-(U2-PC2(ADC2)-Pad25)") (class "Default")
      (node (ref "U2") (pin "25") (pinfunction "PC2(ADC2)_25") (pintype "bidirectional"))
    )
    (net (code "140") (name "unconnected-(U2-PC3(ADC3)-Pad26)") (class "Default")
      (node (ref "U2") (pin "26") (pinfunction "PC3(ADC3)_26") (pintype "bidirectional"))
    )
    (net (code "141") (name "unconnected-(U2-PC4(ADC4{slash}SDA)-Pad27)") (class "Default")
      (node (ref "U2") (pin "27") (pinfunction "PC4(ADC4/SDA)_27") (pintype "bidirectional"))
    )
    (net (code "142") (name "unconnected-(U2-PC5(ADC5{slash}SCL)-Pad28)") (class "Default")
      (node (ref "U2") (pin "28") (pinfunction "PC5(ADC5/SCL)_28") (pintype "bidirectional"))
    )
    (net (code "143") (name "unconnected-(U2-PD0(RXD)-Pad2)") (class "Default")
      (node (ref "U2") (pin "2") (pinfunction "PD0(RXD)_2") (pintype "bidirectional"))
    )
    (net (code "144") (name "unconnected-(U2-PD1(TXD)-Pad3)") (class "Default")
      (node (ref "U2") (pin "3") (pinfunction "PD1(TXD)_3") (pintype "bidirectional"))
    )
    (net (code "145") (name "unconnected-(X1-Pad1)") (class "Default")
      (node (ref "X1") (pin "1") (pinfunction "1_1") (pintype "passive"))
    )
    (net (code "146") (name "unconnected-(X1-Pad2)") (class "Default")
      (node (ref "X1") (pin "2") (pinfunction "2_2") (pintype "passive"))
    )
    (net (code "147") (name "unconnected-(X1-Pad3)") (class "Default")
      (node (ref "X1") (pin "3") (pinfunction "3_3") (pintype "passive"))
    )
    (net (code "148") (name "unconnected-(X1-Pad7)") (class "Default")
      (node (ref "X1") (pin "7") (pinfunction "7_7") (pintype "passive"))
    )
    (net (code "149") (name "unconnected-(X1-Pad8)") (class "Default")
      (node (ref "X1") (pin "8") (pinfunction "8_8") (pintype "passive"))
    )
    (net (code "150") (name "unconnected-(X1-Pad9)") (class "Default")
      (node (ref "X1") (pin "9") (pinfunction "9_9") (pintype "passive"))
    )
    (net (code "151") (name "unconnected-(X1-Pad10)") (class "Default")
      (node (ref "X1") (pin "10") (pinfunction "10_10") (pintype "passive"))
    )
    (net (code "152") (name "unconnected-(X1-Pad11)") (class "Default")
      (node (ref "X1") (pin "11") (pinfunction "11_11") (pintype "passive"))
    )
    (net (code "153") (name "unconnected-(X1-Pad12)") (class "Default")
      (node (ref "X1") (pin "12") (pinfunction "12_12") (pintype "passive"))
    )
    (net (code "154") (name "unconnected-(X1-Pad14)") (class "Default")
      (node (ref "X1") (pin "14") (pinfunction "14_14") (pintype "passive"))
    )
    (net (code "155") (name "unconnected-(X1-Pad15)") (class "Default")
      (node (ref "X1") (pin "15") (pinfunction "15_15") (pintype "passive"))
    )
    (net (code "156") (name "unconnected-(X1-Pad16)") (class "Default")
      (node (ref "X1") (pin "16") (pinfunction "16_16") (pintype "passive"))
    )
    (net (code "157") (name "unconnected-(X1-Pad17)") (class "Default")
      (node (ref "X1") (pin "17") (pinfunction "17_17") (pintype "passive"))
    )
    (net (code "158") (name "unconnected-(X1-Pad18)") (class "Default")
      (node (ref "X1") (pin "18") (pinfunction "18_18") (pintype "passive"))
    )
    (net (code "159") (name "unconnected-(X1-Pad19)") (class "Default")
      (node (ref "X1") (pin "19") (pinfunction "19_19") (pintype "passive"))
    )
    (net (code "160") (name "unconnected-(X1-Pad20)") (class "Default")
      (node (ref "X1") (pin "20") (pinfunction "20_20") (pintype "passive"))
    )
    (net (code "161") (name "unconnected-(X1-Pad21)") (class "Default")
      (node (ref "X1") (pin "21") (pinfunction "21_21") (pintype "passive"))
    )
    (net (code "162") (name "unconnected-(X1-Pad22)") (class "Default")
      (node (ref "X1") (pin "22") (pinfunction "22_22") (pintype "passive"))
    )
    (net (code "163") (name "unconnected-(X1-Pad23)") (class "Default")
      (node (ref "X1") (pin "23") (pinfunction "23_23") (pintype "passive"))
    )
    (net (code "164") (name "unconnected-(X1-Pad24)") (class "Default")
      (node (ref "X1") (pin "24") (pinfunction "24_24") (pintype "passive"))
    )
    (net (code "165") (name "unconnected-(X1-Pad25)") (class "Default")
      (node (ref "X1") (pin "25") (pinfunction "25_25") (pintype "passive"))
    )
  )
)
